# MCU2.net
KiCad netlist of a schematic drawn in Altium Designer
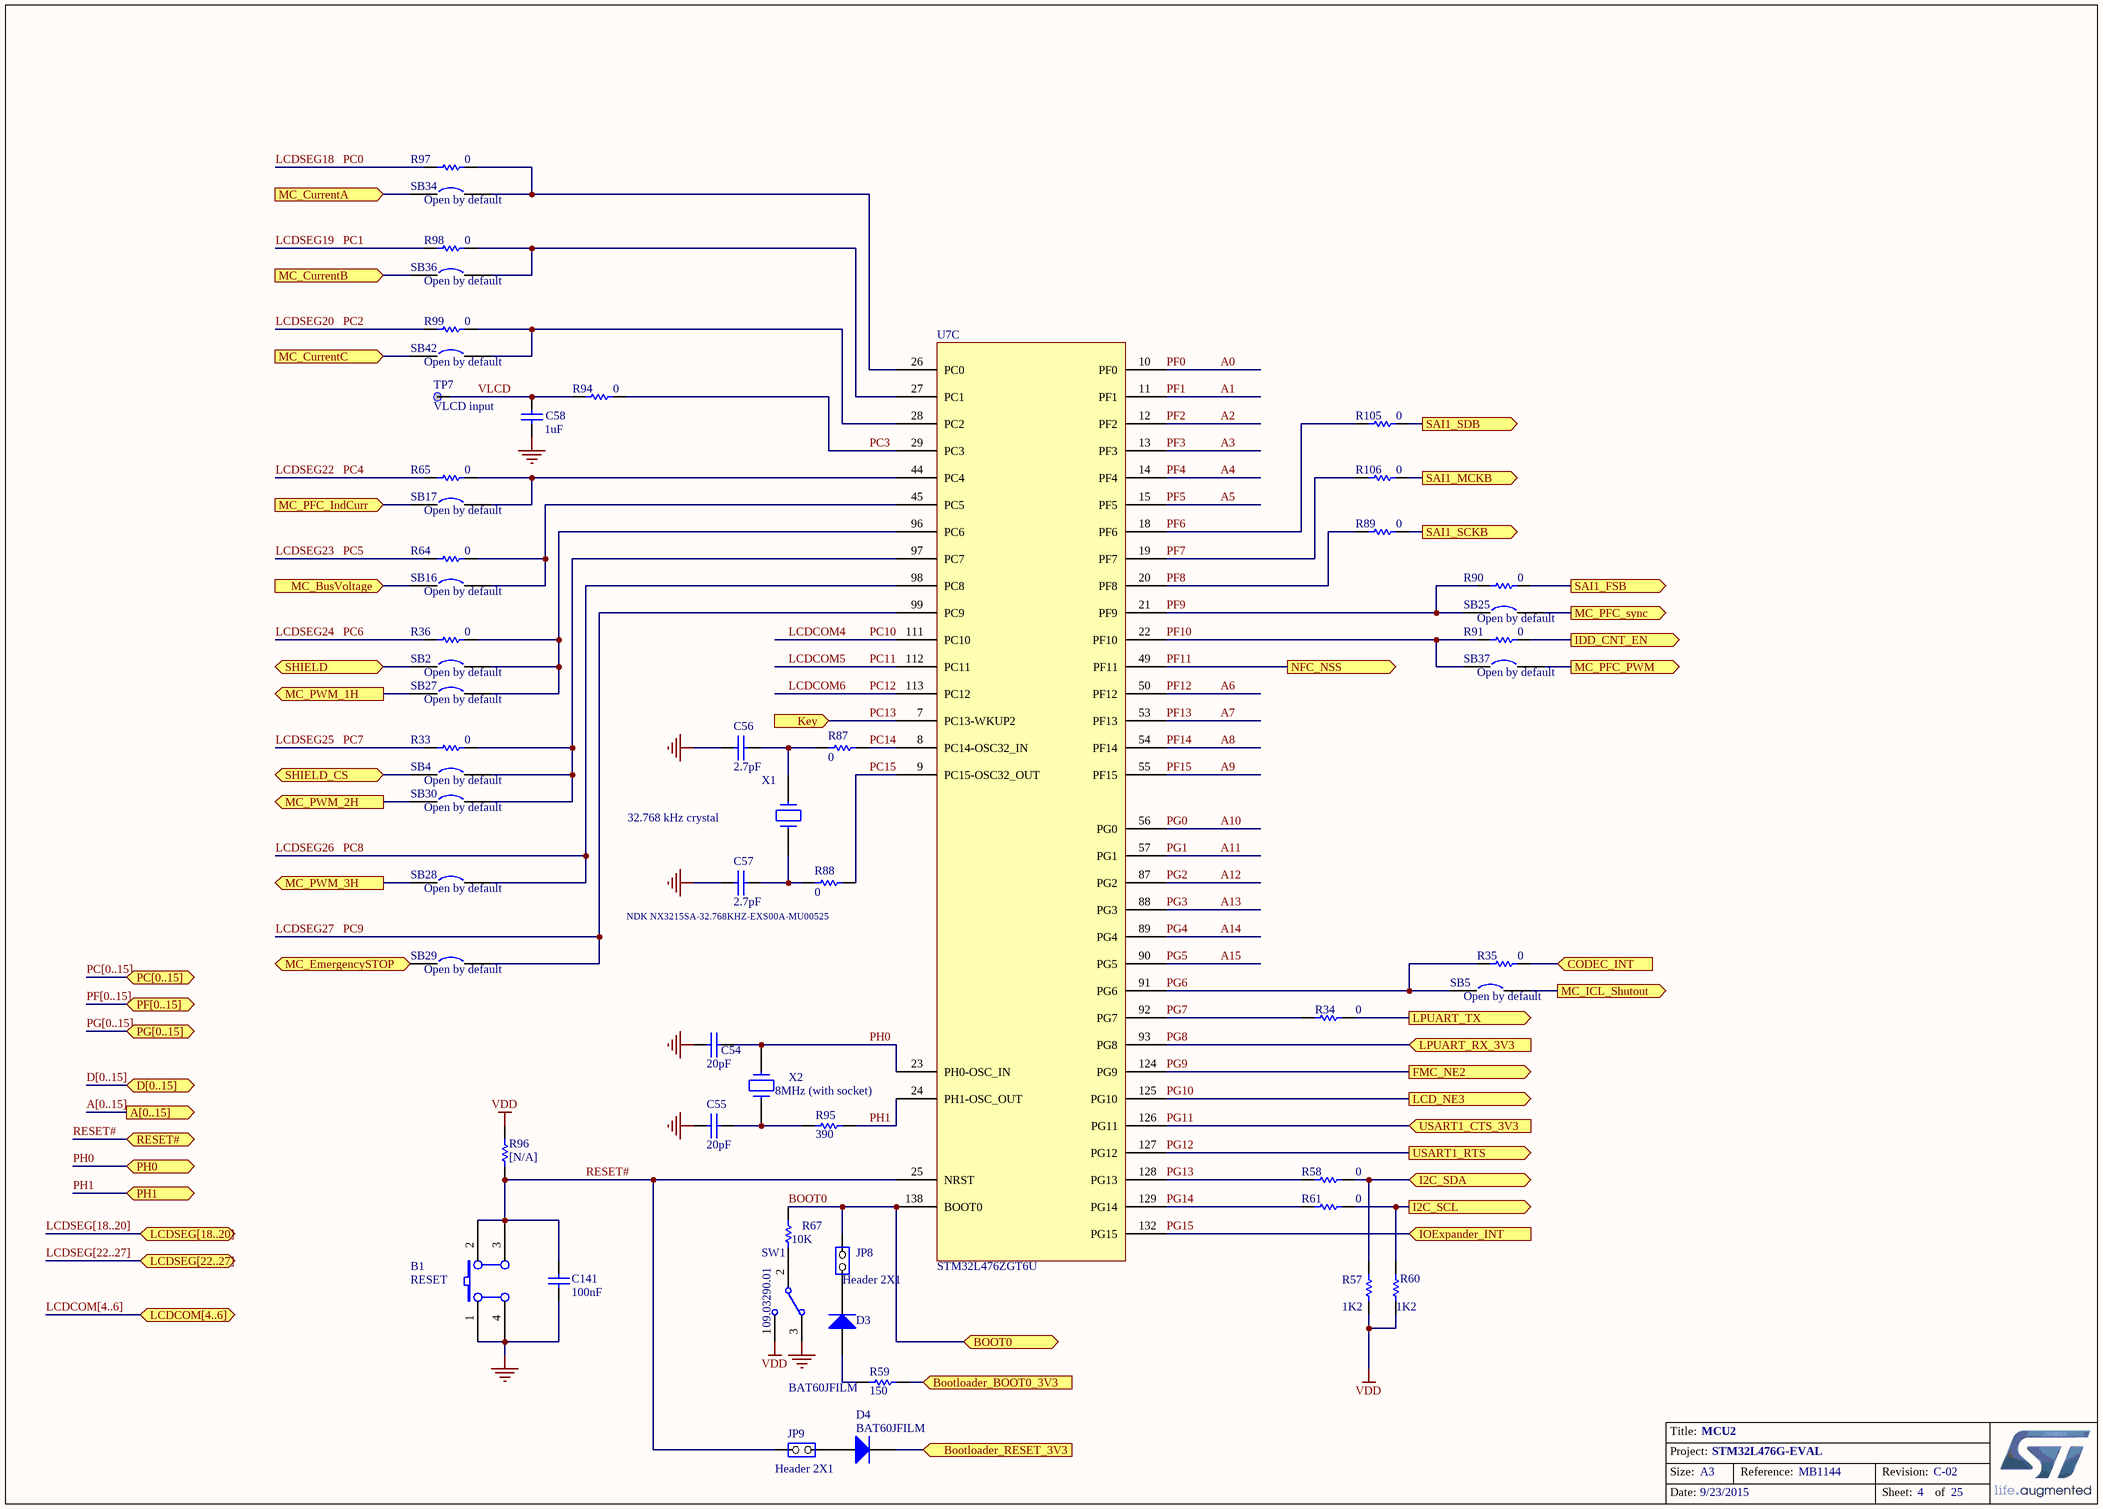
[diagram p0: MCU2.SchDoc]

(export (version "E")
  (design (tool "Eeschema 10.0.6"))
  (components
    (comp (ref "B1")
      (value "RESET")
      (footprint "PB10")
      (description "SE PUSHBUTTON")
      (libsource (lib "Documents") (part "SW PUSHBUTTON"))
    )
    (comp (ref "C54")
      (value "20pF")
      (footprint "0402R")
      (description "Capacitor")
      (libsource (lib "*") (part "CAP"))
    )
    (comp (ref "C55")
      (value "20pF")
      (footprint "0402R")
      (description "Capacitor")
      (libsource (lib "*") (part "CAP"))
    )
    (comp (ref "C56")
      (value "2.7pF")
      (footprint "0603C")
      (description "Capacitor")
      (libsource (lib "") (part "CAP_1"))
    )
    (comp (ref "C57")
      (value "2.7pF")
      (footprint "0603C")
      (description "Capacitor")
      (libsource (lib "") (part "CAP_1"))
    )
    (comp (ref "C58")
      (value "1uF")
      (footprint "0603C")
      (description "Capacitor")
      (fields (field (name "PUBLISHER") "Altium Limited"))
      (libsource (lib "Miscellaneous Devices") (part "CAP"))
    )
    (comp (ref "C141")
      (value "100nF")
      (footprint "0402C")
      (description "Capacitor")
      (fields (field (name "PUBLISHER") "Altium Limited"))
      (libsource (lib "Miscellaneous Devices") (part "CAP"))
    )
    (comp (ref "D3")
      (value "BAT60JFILM")
      (footprint "SOD-323")
      (description "Default Diode")
      (fields (field (name "PUBLISHER") "Altium Limited"))
      (libsource (lib "Miscellaneous Devices") (part "Diode"))
    )
    (comp (ref "D4")
      (value "BAT60JFILM")
      (footprint "SOD-323")
      (description "Default Diode")
      (fields (field (name "PUBLISHER") "Altium Limited"))
      (libsource (lib "Miscellaneous Devices") (part "Diode"))
    )
    (comp (ref "JP8") (value "Header 2X1") (footprint "SIP2") (libsource (lib "*") (part "JP2")))
    (comp (ref "JP9") (value "Header 2X1") (footprint "SIP2") (libsource (lib "*") (part "JP2")))
    (comp (ref "R33")
      (value "0")
      (footprint "SB_0603")
      (description "Resistor")
      (fields (field (name "PUBLISHER") "Altium Limited"))
      (libsource (lib "Miscellaneous Devices") (part "Res1"))
    )
    (comp (ref "R34")
      (value "0")
      (footprint "0603R")
      (description "Resistor")
      (fields (field (name "PUBLISHER") "Altium Limited"))
      (libsource (lib "") (part "Res1_1"))
    )
    (comp (ref "R35")
      (value "0")
      (footprint "SB_0603")
      (description "Resistor")
      (fields (field (name "PUBLISHER") "Altium Limited"))
      (libsource (lib "Miscellaneous Devices") (part "res1"))
    )
    (comp (ref "R36")
      (value "0")
      (footprint "SB_0603")
      (description "Resistor")
      (fields (field (name "PUBLISHER") "Altium Limited"))
      (libsource (lib "Miscellaneous Devices") (part "Res1"))
    )
    (comp (ref "R57")
      (value "1K2")
      (footprint "0402R")
      (description "Resistor")
      (fields (field (name "PUBLISHER") "Altium Limited"))
      (libsource (lib "") (part "Res1_1"))
    )
    (comp (ref "R58")
      (value "0")
      (footprint "0603R")
      (description "Resistor")
      (fields (field (name "PUBLISHER") "Altium Limited"))
      (libsource (lib "") (part "Res1_1"))
    )
    (comp (ref "R59")
      (value "150")
      (footprint "0402R")
      (description "Resistor")
      (fields (field (name "PUBLISHER") "Altium Limited"))
      (libsource (lib "Miscellaneous Devices") (part "res1"))
    )
    (comp (ref "R60")
      (value "1K2")
      (footprint "0402R")
      (description "Resistor")
      (fields (field (name "PUBLISHER") "Altium Limited"))
      (libsource (lib "") (part "Res1_1"))
    )
    (comp (ref "R61")
      (value "0")
      (footprint "0603R")
      (description "Resistor")
      (fields (field (name "PUBLISHER") "Altium Limited"))
      (libsource (lib "") (part "Res1_1"))
    )
    (comp (ref "R64")
      (value "0")
      (footprint "SB_0603")
      (description "Resistor")
      (fields (field (name "PUBLISHER") "Altium Limited"))
      (libsource (lib "Miscellaneous Devices") (part "Res1"))
    )
    (comp (ref "R65")
      (value "0")
      (footprint "SB_0603")
      (description "Resistor")
      (fields (field (name "PUBLISHER") "Altium Limited"))
      (libsource (lib "Miscellaneous Devices") (part "Res1"))
    )
    (comp (ref "R67")
      (value "10K")
      (footprint "0402R")
      (description "Resistor")
      (fields (field (name "PUBLISHER") "Altium Limited"))
      (libsource (lib "Miscellaneous Devices") (part "res1"))
    )
    (comp (ref "R87")
      (value "0")
      (footprint "0603R")
      (description "Resistor")
      (fields (field (name "PUBLISHER") "Altium Limited"))
      (libsource (lib "Miscellaneous Devices") (part "Res1"))
    )
    (comp (ref "R88")
      (value "0")
      (footprint "0603R")
      (description "Resistor")
      (fields (field (name "PUBLISHER") "Altium Limited"))
      (libsource (lib "Miscellaneous Devices") (part "Res1"))
    )
    (comp (ref "R89")
      (value "0")
      (footprint "0603R")
      (description "Resistor")
      (fields (field (name "PUBLISHER") "Altium Limited"))
      (libsource (lib "Miscellaneous Devices") (part "res1"))
    )
    (comp (ref "R90")
      (value "0")
      (footprint "SB_0603")
      (description "Resistor")
      (fields (field (name "PUBLISHER") "Altium Limited"))
      (libsource (lib "Miscellaneous Devices") (part "res1"))
    )
    (comp (ref "R91")
      (value "0")
      (footprint "SB_0603")
      (description "Resistor")
      (fields (field (name "PUBLISHER") "Altium Limited"))
      (libsource (lib "Miscellaneous Devices") (part "res1"))
    )
    (comp (ref "R94")
      (value "0")
      (footprint "0603R")
      (description "Resistor")
      (fields (field (name "PUBLISHER") "Altium Limited"))
      (libsource (lib "Miscellaneous Devices") (part "res1"))
    )
    (comp (ref "R95")
      (value "390")
      (footprint "0603R")
      (description "Resistor")
      (fields (field (name "PUBLISHER") "Altium Limited"))
      (libsource (lib "") (part "Res1_1"))
    )
    (comp (ref "R96")
      (value "[N/A]")
      (footprint "0603R")
      (description "Resistor")
      (fields (field (name "PUBLISHER") "Altium Limited"))
      (libsource (lib "Miscellaneous Devices") (part "res1"))
    )
    (comp (ref "R97")
      (value "0")
      (footprint "SB_0603")
      (description "Resistor")
      (fields (field (name "PUBLISHER") "Altium Limited"))
      (libsource (lib "Miscellaneous Devices") (part "Res1"))
    )
    (comp (ref "R98")
      (value "0")
      (footprint "SB_0603")
      (description "Resistor")
      (fields (field (name "PUBLISHER") "Altium Limited"))
      (libsource (lib "Miscellaneous Devices") (part "Res1"))
    )
    (comp (ref "R99")
      (value "0")
      (footprint "SB_0603")
      (description "Resistor")
      (fields (field (name "PUBLISHER") "Altium Limited"))
      (libsource (lib "Miscellaneous Devices") (part "Res1"))
    )
    (comp (ref "R105")
      (value "0")
      (footprint "0603R")
      (description "Resistor")
      (fields (field (name "PUBLISHER") "Altium Limited"))
      (libsource (lib "Miscellaneous Devices") (part "res1"))
    )
    (comp (ref "R106")
      (value "0")
      (footprint "0603R")
      (description "Resistor")
      (fields (field (name "PUBLISHER") "Altium Limited"))
      (libsource (lib "Miscellaneous Devices") (part "res1"))
    )
    (comp (ref "SB2")
      (value "Open by default")
      (footprint "SB_0603")
      (description "Circuit Breaker")
      (fields (field (name "PUBLISHER") "Altium Limited"))
      (libsource (lib "Miscellaneous Devices") (part "Circuit Breaker"))
    )
    (comp (ref "SB4")
      (value "Open by default")
      (footprint "SB_0603")
      (description "Circuit Breaker")
      (fields (field (name "PUBLISHER") "Altium Limited"))
      (libsource (lib "Miscellaneous Devices") (part "Circuit Breaker"))
    )
    (comp (ref "SB5")
      (value "Open by default")
      (footprint "SB_0603")
      (description "Circuit Breaker")
      (fields (field (name "PUBLISHER") "Altium Limited"))
      (libsource (lib "Miscellaneous Devices") (part "Circuit Breaker"))
    )
    (comp (ref "SB16")
      (value "Open by default")
      (footprint "SB_0603")
      (description "Circuit Breaker")
      (fields (field (name "PUBLISHER") "Altium Limited"))
      (libsource (lib "Miscellaneous Devices") (part "Circuit Breaker"))
    )
    (comp (ref "SB17")
      (value "Open by default")
      (footprint "SB_0603")
      (description "Circuit Breaker")
      (fields (field (name "PUBLISHER") "Altium Limited"))
      (libsource (lib "Miscellaneous Devices") (part "Circuit Breaker"))
    )
    (comp (ref "SB25")
      (value "Open by default")
      (footprint "SB_0603")
      (description "Circuit Breaker")
      (fields (field (name "PUBLISHER") "Altium Limited"))
      (libsource (lib "Miscellaneous Devices") (part "Circuit Breaker"))
    )
    (comp (ref "SB27")
      (value "Open by default")
      (footprint "SB_0603")
      (description "Circuit Breaker")
      (fields (field (name "PUBLISHER") "Altium Limited"))
      (libsource (lib "Miscellaneous Devices") (part "Circuit Breaker"))
    )
    (comp (ref "SB28")
      (value "Open by default")
      (footprint "SB_0603")
      (description "Circuit Breaker")
      (fields (field (name "PUBLISHER") "Altium Limited"))
      (libsource (lib "Miscellaneous Devices") (part "Circuit Breaker"))
    )
    (comp (ref "SB29")
      (value "Open by default")
      (footprint "SB_0603")
      (description "Circuit Breaker")
      (fields (field (name "PUBLISHER") "Altium Limited"))
      (libsource (lib "Miscellaneous Devices") (part "Circuit Breaker"))
    )
    (comp (ref "SB30")
      (value "Open by default")
      (footprint "SB_0603")
      (description "Circuit Breaker")
      (fields (field (name "PUBLISHER") "Altium Limited"))
      (libsource (lib "Miscellaneous Devices") (part "Circuit Breaker"))
    )
    (comp (ref "SB34")
      (value "Open by default")
      (footprint "SB_0603")
      (description "Circuit Breaker")
      (fields (field (name "PUBLISHER") "Altium Limited"))
      (libsource (lib "Miscellaneous Devices") (part "Circuit Breaker"))
    )
    (comp (ref "SB36")
      (value "Open by default")
      (footprint "SB_0603")
      (description "Circuit Breaker")
      (fields (field (name "PUBLISHER") "Altium Limited"))
      (libsource (lib "Miscellaneous Devices") (part "Circuit Breaker"))
    )
    (comp (ref "SB37")
      (value "Open by default")
      (footprint "SB_0603")
      (description "Circuit Breaker")
      (fields (field (name "PUBLISHER") "Altium Limited"))
      (libsource (lib "Miscellaneous Devices") (part "Circuit Breaker"))
    )
    (comp (ref "SB42")
      (value "Open by default")
      (footprint "SB_0603")
      (description "Circuit Breaker")
      (fields (field (name "PUBLISHER") "Altium Limited"))
      (libsource (lib "Miscellaneous Devices") (part "Circuit Breaker"))
    )
    (comp (ref "SW1")
      (value "09.03290.01")
      (footprint "SW1_3TH_2R54_10X2R5")
      (description "SPDT Subminiature Toggle Switch, Right Angle Mounting, Vertical Actuation")
      (fields (field (name "PUBLISHER") "Altium Limited"))
      (libsource (lib "Miscellaneous Devices") (part "SW-SPDT"))
    )
    (comp (ref "TP7")
      (value "[N/A]")
      (footprint "TP")
      (fields (field (name "TP NAME") "VLCD input"))
      (libsource (lib "orca2") (part "TP"))
    )
    (comp (ref "U7")
      (value "STM32L476ZGT6U")
      (footprint "TQFP144_0R5_22X22_SOCKET")
      (libsource (lib "MB1144") (part "STM32L476_TQFP144"))
    )
    (comp (ref "X1")
      (value "NDK NX3215SA-32.768KHZ-EXS00A-MU00525")
      (footprint "XTAL_2SM_3R2X1R5")
      (description "Crystal")
      (libsource (lib "MB1167") (part "CRYSTAL_32K"))
    )
    (comp (ref "X2")
      (value "8MHz (with socket)")
      (footprint "XTAL_SOCKET")
      (description "Crystal")
      (libsource (lib "*") (part "CRYSTAL"))
    )
  )
  (nets
    (net (code "17") (name "/A10") (class "Default")
      (node (ref "U7") (pin "56") (pinfunction "PG0_56") (pintype "passive"))
    )
    (net (code "18") (name "/A11") (class "Default")
      (node (ref "U7") (pin "57") (pinfunction "PG1_57") (pintype "passive"))
    )
    (net (code "19") (name "/A12") (class "Default")
      (node (ref "U7") (pin "87") (pinfunction "PG2_87") (pintype "passive"))
    )
    (net (code "20") (name "/A13") (class "Default")
      (node (ref "U7") (pin "88") (pinfunction "PG3_88") (pintype "passive"))
    )
    (net (code "21") (name "/A14") (class "Default")
      (node (ref "U7") (pin "89") (pinfunction "PG4_89") (pintype "passive"))
    )
    (net (code "22") (name "/A15") (class "Default")
      (node (ref "U7") (pin "90") (pinfunction "PG5_90") (pintype "passive"))
    )
    (net (code "24") (name "/BOOT0") (class "Default")
      (node (ref "JP8") (pin "1") (pinfunction "COMMON_1") (pintype "passive"))
      (node (ref "R67") (pin "1") (pinfunction "1_1") (pintype "passive"))
      (node (ref "U7") (pin "138") (pinfunction "BOOT0_138") (pintype "passive"))
    )
    (net (code "25") (name "/Bootloader_BOOT0_3V3") (class "Default")
      (node (ref "R59") (pin "2") (pinfunction "2_2") (pintype "passive"))
    )
    (net (code "26") (name "/Bootloader_RESET_3V3") (class "Default")
      (node (ref "D4") (pin "2") (pinfunction "K_2") (pintype "passive"))
    )
    (net (code "27") (name "/CODEC_INT") (class "Default")
      (node (ref "R35") (pin "1") (pinfunction "1_1") (pintype "passive"))
    )
    (net (code "29") (name "/I2C_SCL") (class "Default")
      (node (ref "R60") (pin "1") (pinfunction "1_1") (pintype "passive"))
      (node (ref "R61") (pin "1") (pinfunction "1_1") (pintype "passive"))
    )
    (net (code "30") (name "/I2C_SDA") (class "Default")
      (node (ref "R57") (pin "1") (pinfunction "1_1") (pintype "passive"))
      (node (ref "R58") (pin "1") (pinfunction "1_1") (pintype "passive"))
    )
    (net (code "31") (name "/IDD_CNT_EN") (class "Default")
      (node (ref "R91") (pin "1") (pinfunction "1_1") (pintype "passive"))
    )
    (net (code "35") (name "/LPUART_TX") (class "Default")
      (node (ref "R34") (pin "1") (pinfunction "1_1") (pintype "passive"))
    )
    (net (code "36") (name "/MC_BusVoltage") (class "Default")
      (node (ref "SB16") (pin "1") (pinfunction "1_1") (pintype "passive"))
    )
    (net (code "37") (name "/MC_CurrentA") (class "Default")
      (node (ref "SB34") (pin "1") (pinfunction "1_1") (pintype "passive"))
    )
    (net (code "38") (name "/MC_CurrentB") (class "Default")
      (node (ref "SB36") (pin "1") (pinfunction "1_1") (pintype "passive"))
    )
    (net (code "39") (name "/MC_CurrentC") (class "Default")
      (node (ref "SB42") (pin "1") (pinfunction "1_1") (pintype "passive"))
    )
    (net (code "40") (name "/MC_EmergencySTOP") (class "Default")
      (node (ref "SB29") (pin "1") (pinfunction "1_1") (pintype "passive"))
    )
    (net (code "41") (name "/MC_ICL_Shutout") (class "Default")
      (node (ref "SB5") (pin "2") (pinfunction "2_2") (pintype "passive"))
    )
    (net (code "42") (name "/MC_PFC_IndCurr") (class "Default")
      (node (ref "SB17") (pin "1") (pinfunction "1_1") (pintype "passive"))
    )
    (net (code "43") (name "/MC_PFC_PWM") (class "Default")
      (node (ref "SB37") (pin "2") (pinfunction "2_2") (pintype "passive"))
    )
    (net (code "44") (name "/MC_PFC_sync") (class "Default")
      (node (ref "SB25") (pin "2") (pinfunction "2_2") (pintype "passive"))
    )
    (net (code "45") (name "/MC_PWM_1H") (class "Default")
      (node (ref "SB27") (pin "1") (pinfunction "1_1") (pintype "passive"))
    )
    (net (code "46") (name "/MC_PWM_2H") (class "Default")
      (node (ref "SB30") (pin "1") (pinfunction "1_1") (pintype "passive"))
    )
    (net (code "47") (name "/MC_PWM_3H") (class "Default")
      (node (ref "SB28") (pin "1") (pinfunction "1_1") (pintype "passive"))
    )
    (net (code "48") (name "/PC0") (class "Default")
      (node (ref "R97") (pin "1") (pinfunction "1_1") (pintype "passive"))
    )
    (net (code "49") (name "/PC1") (class "Default")
      (node (ref "R98") (pin "1") (pinfunction "1_1") (pintype "passive"))
    )
    (net (code "50") (name "/PC2") (class "Default")
      (node (ref "R99") (pin "1") (pinfunction "1_1") (pintype "passive"))
    )
    (net (code "51") (name "/PC3") (class "Default")
      (node (ref "R94") (pin "1") (pinfunction "1_1") (pintype "passive"))
      (node (ref "U7") (pin "29") (pinfunction "PC3_29") (pintype "passive"))
    )
    (net (code "52") (name "/PC4") (class "Default")
      (node (ref "R65") (pin "1") (pinfunction "1_1") (pintype "passive"))
    )
    (net (code "53") (name "/PC5") (class "Default")
      (node (ref "R64") (pin "1") (pinfunction "1_1") (pintype "passive"))
    )
    (net (code "54") (name "/PC6") (class "Default")
      (node (ref "R36") (pin "1") (pinfunction "1_1") (pintype "passive"))
    )
    (net (code "55") (name "/PC7") (class "Default")
      (node (ref "R33") (pin "1") (pinfunction "1_1") (pintype "passive"))
    )
    (net (code "56") (name "/PC8") (class "Default")
      (node (ref "SB28") (pin "2") (pinfunction "2_2") (pintype "passive"))
      (node (ref "U7") (pin "98") (pinfunction "PC8_98") (pintype "passive"))
    )
    (net (code "57") (name "/PC9") (class "Default")
      (node (ref "SB29") (pin "2") (pinfunction "2_2") (pintype "passive"))
      (node (ref "U7") (pin "99") (pinfunction "PC9_99") (pintype "passive"))
    )
    (net (code "58") (name "/PC10") (class "Default")
      (node (ref "U7") (pin "111") (pinfunction "PC10_111") (pintype "passive"))
    )
    (net (code "59") (name "/PC11") (class "Default")
      (node (ref "U7") (pin "112") (pinfunction "PC11_112") (pintype "passive"))
    )
    (net (code "60") (name "/PC12") (class "Default")
      (node (ref "U7") (pin "113") (pinfunction "PC12_113") (pintype "passive"))
    )
    (net (code "61") (name "/PC13") (class "Default")
      (node (ref "U7") (pin "7") (pinfunction "PC13-WKUP2_7") (pintype "passive"))
    )
    (net (code "62") (name "/PC14") (class "Default")
      (node (ref "R87") (pin "2") (pinfunction "2_2") (pintype "passive"))
      (node (ref "U7") (pin "8") (pinfunction "PC14-OSC32_IN_8") (pintype "passive"))
    )
    (net (code "63") (name "/PC15") (class "Default")
      (node (ref "R88") (pin "2") (pinfunction "2_2") (pintype "passive"))
      (node (ref "U7") (pin "9") (pinfunction "PC15-OSC32_OUT_9") (pintype "passive"))
    )
    (net (code "65") (name "/PF0") (class "Default")
      (node (ref "U7") (pin "10") (pinfunction "PF0_10") (pintype "passive"))
    )
    (net (code "66") (name "/PF1") (class "Default")
      (node (ref "U7") (pin "11") (pinfunction "PF1_11") (pintype "passive"))
    )
    (net (code "67") (name "/PF2") (class "Default")
      (node (ref "U7") (pin "12") (pinfunction "PF2_12") (pintype "passive"))
    )
    (net (code "68") (name "/PF3") (class "Default")
      (node (ref "U7") (pin "13") (pinfunction "PF3_13") (pintype "passive"))
    )
    (net (code "69") (name "/PF4") (class "Default")
      (node (ref "U7") (pin "14") (pinfunction "PF4_14") (pintype "passive"))
    )
    (net (code "70") (name "/PF5") (class "Default")
      (node (ref "U7") (pin "15") (pinfunction "PF5_15") (pintype "passive"))
    )
    (net (code "71") (name "/PF6") (class "Default")
      (node (ref "R105") (pin "2") (pinfunction "2_2") (pintype "passive"))
      (node (ref "U7") (pin "18") (pinfunction "PF6_18") (pintype "passive"))
    )
    (net (code "72") (name "/PF7") (class "Default")
      (node (ref "R106") (pin "2") (pinfunction "2_2") (pintype "passive"))
      (node (ref "U7") (pin "19") (pinfunction "PF7_19") (pintype "passive"))
    )
    (net (code "73") (name "/PF8") (class "Default")
      (node (ref "R89") (pin "2") (pinfunction "2_2") (pintype "passive"))
      (node (ref "U7") (pin "20") (pinfunction "PF8_20") (pintype "passive"))
    )
    (net (code "74") (name "/PF9") (class "Default")
      (node (ref "R90") (pin "2") (pinfunction "2_2") (pintype "passive"))
      (node (ref "SB25") (pin "1") (pinfunction "1_1") (pintype "passive"))
      (node (ref "U7") (pin "21") (pinfunction "PF9_21") (pintype "passive"))
    )
    (net (code "75") (name "/PF10") (class "Default")
      (node (ref "R91") (pin "2") (pinfunction "2_2") (pintype "passive"))
      (node (ref "SB37") (pin "1") (pinfunction "1_1") (pintype "passive"))
      (node (ref "U7") (pin "22") (pinfunction "PF10_22") (pintype "passive"))
    )
    (net (code "76") (name "/PF11") (class "Default")
      (node (ref "U7") (pin "49") (pinfunction "PF11_49") (pintype "passive"))
    )
    (net (code "77") (name "/PF12") (class "Default")
      (node (ref "U7") (pin "50") (pinfunction "PF12_50") (pintype "passive"))
    )
    (net (code "78") (name "/PF13") (class "Default")
      (node (ref "U7") (pin "53") (pinfunction "PF13_53") (pintype "passive"))
    )
    (net (code "79") (name "/PF14") (class "Default")
      (node (ref "U7") (pin "54") (pinfunction "PF14_54") (pintype "passive"))
    )
    (net (code "80") (name "/PF15") (class "Default")
      (node (ref "U7") (pin "55") (pinfunction "PF15_55") (pintype "passive"))
    )
    (net (code "82") (name "/PG6") (class "Default")
      (node (ref "R35") (pin "2") (pinfunction "2_2") (pintype "passive"))
      (node (ref "SB5") (pin "1") (pinfunction "1_1") (pintype "passive"))
      (node (ref "U7") (pin "91") (pinfunction "PG6_91") (pintype "passive"))
    )
    (net (code "83") (name "/PG7") (class "Default")
      (node (ref "R34") (pin "2") (pinfunction "2_2") (pintype "passive"))
      (node (ref "U7") (pin "92") (pinfunction "PG7_92") (pintype "passive"))
    )
    (net (code "84") (name "/PG8") (class "Default")
      (node (ref "U7") (pin "93") (pinfunction "PG8_93") (pintype "passive"))
    )
    (net (code "85") (name "/PG9") (class "Default")
      (node (ref "U7") (pin "124") (pinfunction "PG9_124") (pintype "passive"))
    )
    (net (code "86") (name "/PG10") (class "Default")
      (node (ref "U7") (pin "125") (pinfunction "PG10_125") (pintype "passive"))
    )
    (net (code "87") (name "/PG11") (class "Default")
      (node (ref "U7") (pin "126") (pinfunction "PG11_126") (pintype "passive"))
    )
    (net (code "88") (name "/PG12") (class "Default")
      (node (ref "U7") (pin "127") (pinfunction "PG12_127") (pintype "passive"))
    )
    (net (code "89") (name "/PG13") (class "Default")
      (node (ref "R58") (pin "2") (pinfunction "2_2") (pintype "passive"))
      (node (ref "U7") (pin "128") (pinfunction "PG13_128") (pintype "passive"))
    )
    (net (code "90") (name "/PG14") (class "Default")
      (node (ref "R61") (pin "2") (pinfunction "2_2") (pintype "passive"))
      (node (ref "U7") (pin "129") (pinfunction "PG14_129") (pintype "passive"))
    )
    (net (code "91") (name "/PG15") (class "Default")
      (node (ref "U7") (pin "132") (pinfunction "PG15_132") (pintype "passive"))
    )
    (net (code "93") (name "/PH0") (class "Default")
      (node (ref "C54") (pin "1") (pinfunction "1_1") (pintype "passive"))
      (node (ref "U7") (pin "23") (pinfunction "PH0-OSC_IN_23") (pintype "passive"))
      (node (ref "X2") (pin "2") (pinfunction "2_2") (pintype "passive"))
    )
    (net (code "94") (name "/PH1") (class "Default")
      (node (ref "R95") (pin "1") (pinfunction "1_1") (pintype "passive"))
      (node (ref "U7") (pin "24") (pinfunction "PH1-OSC_OUT_24") (pintype "passive"))
    )
    (net (code "95") (name "/RESET#") (class "Default")
      (node (ref "B1") (pin "2") (pinfunction "B0_2") (pintype "passive"))
      (node (ref "B1") (pin "3") (pinfunction "B1_3") (pintype "passive"))
      (node (ref "C141") (pin "2") (pinfunction "2_2") (pintype "passive"))
      (node (ref "JP9") (pin "1") (pinfunction "COMMON_1") (pintype "passive"))
      (node (ref "R96") (pin "1") (pinfunction "1_1") (pintype "passive"))
      (node (ref "U7") (pin "25") (pinfunction "NRST_25") (pintype "passive"))
    )
    (net (code "96") (name "/SAI1_FSB") (class "Default")
      (node (ref "R90") (pin "1") (pinfunction "1_1") (pintype "passive"))
    )
    (net (code "97") (name "/SAI1_MCKB") (class "Default")
      (node (ref "R106") (pin "1") (pinfunction "1_1") (pintype "passive"))
    )
    (net (code "98") (name "/SAI1_SCKB") (class "Default")
      (node (ref "R89") (pin "1") (pinfunction "1_1") (pintype "passive"))
    )
    (net (code "99") (name "/SAI1_SDB") (class "Default")
      (node (ref "R105") (pin "1") (pinfunction "1_1") (pintype "passive"))
    )
    (net (code "100") (name "/SHIELD") (class "Default")
      (node (ref "SB2") (pin "1") (pinfunction "1_1") (pintype "passive"))
    )
    (net (code "101") (name "/SHIELD_CS") (class "Default")
      (node (ref "SB4") (pin "1") (pinfunction "1_1") (pintype "passive"))
    )
    (net (code "102") (name "/VLCD") (class "Default")
      (node (ref "C58") (pin "2") (pinfunction "2_2") (pintype "passive"))
      (node (ref "R94") (pin "2") (pinfunction "2_2") (pintype "passive"))
      (node (ref "TP7") (pin "1") (pinfunction "1_1") (pintype "passive"))
    )
    (net (code "103") (name "GND") (class "Default")
      (node (ref "B1") (pin "1") (pinfunction "A0_1") (pintype "passive"))
      (node (ref "B1") (pin "4") (pinfunction "A1_4") (pintype "passive"))
      (node (ref "C141") (pin "1") (pinfunction "1_1") (pintype "passive"))
      (node (ref "C54") (pin "2") (pinfunction "2_2") (pintype "passive"))
      (node (ref "C55") (pin "2") (pinfunction "2_2") (pintype "passive"))
      (node (ref "C56") (pin "2") (pinfunction "2_2") (pintype "passive"))
      (node (ref "C57") (pin "2") (pinfunction "2_2") (pintype "passive"))
      (node (ref "C58") (pin "1") (pinfunction "1_1") (pintype "passive"))
      (node (ref "SW1") (pin "3") (pintype "passive"))
    )
    (net (code "104") (name "Net-(C55-Pad1)") (class "Default")
      (node (ref "C55") (pin "1") (pinfunction "1_1") (pintype "passive"))
      (node (ref "R95") (pin "2") (pinfunction "2_2") (pintype "passive"))
      (node (ref "X2") (pin "1") (pinfunction "1_1") (pintype "passive"))
    )
    (net (code "105") (name "Net-(C56-Pad1)") (class "Default")
      (node (ref "C56") (pin "1") (pinfunction "1_1") (pintype "passive"))
      (node (ref "R87") (pin "1") (pinfunction "1_1") (pintype "passive"))
      (node (ref "X1") (pin "2") (pinfunction "2_2") (pintype "passive"))
    )
    (net (code "106") (name "Net-(C57-Pad1)") (class "Default")
      (node (ref "C57") (pin "1") (pinfunction "1_1") (pintype "passive"))
      (node (ref "R88") (pin "1") (pinfunction "1_1") (pintype "passive"))
      (node (ref "X1") (pin "1") (pinfunction "1_1") (pintype "passive"))
    )
    (net (code "107") (name "Net-(D3-A)") (class "Default")
      (node (ref "D3") (pin "1") (pinfunction "A_1") (pintype "passive"))
      (node (ref "R59") (pin "1") (pinfunction "1_1") (pintype "passive"))
    )
    (net (code "108") (name "Net-(D3-K)") (class "Default")
      (node (ref "D3") (pin "2") (pinfunction "K_2") (pintype "passive"))
      (node (ref "JP8") (pin "2") (pinfunction "NO_2") (pintype "passive"))
    )
    (net (code "109") (name "Net-(D4-A)") (class "Default")
      (node (ref "D4") (pin "1") (pinfunction "A_1") (pintype "passive"))
      (node (ref "JP9") (pin "2") (pinfunction "NO_2") (pintype "passive"))
    )
    (net (code "110") (name "Net-(R67-Pad2)") (class "Default")
      (node (ref "R67") (pin "2") (pinfunction "2_2") (pintype "passive"))
      (node (ref "SW1") (pin "2") (pintype "passive"))
    )
    (net (code "111") (name "Net-(U7C-PC0)") (class "Default")
      (node (ref "R97") (pin "2") (pinfunction "2_2") (pintype "passive"))
      (node (ref "SB34") (pin "2") (pinfunction "2_2") (pintype "passive"))
      (node (ref "U7") (pin "26") (pinfunction "PC0_26") (pintype "passive"))
    )
    (net (code "112") (name "Net-(U7C-PC1)") (class "Default")
      (node (ref "R98") (pin "2") (pinfunction "2_2") (pintype "passive"))
      (node (ref "SB36") (pin "2") (pinfunction "2_2") (pintype "passive"))
      (node (ref "U7") (pin "27") (pinfunction "PC1_27") (pintype "passive"))
    )
    (net (code "113") (name "Net-(U7C-PC2)") (class "Default")
      (node (ref "R99") (pin "2") (pinfunction "2_2") (pintype "passive"))
      (node (ref "SB42") (pin "2") (pinfunction "2_2") (pintype "passive"))
      (node (ref "U7") (pin "28") (pinfunction "PC2_28") (pintype "passive"))
    )
    (net (code "114") (name "Net-(U7C-PC4)") (class "Default")
      (node (ref "R65") (pin "2") (pinfunction "2_2") (pintype "passive"))
      (node (ref "SB17") (pin "2") (pinfunction "2_2") (pintype "passive"))
      (node (ref "U7") (pin "44") (pinfunction "PC4_44") (pintype "passive"))
    )
    (net (code "115") (name "Net-(U7C-PC5)") (class "Default")
      (node (ref "R64") (pin "2") (pinfunction "2_2") (pintype "passive"))
      (node (ref "SB16") (pin "2") (pinfunction "2_2") (pintype "passive"))
      (node (ref "U7") (pin "45") (pinfunction "PC5_45") (pintype "passive"))
    )
    (net (code "116") (name "Net-(U7C-PC6)") (class "Default")
      (node (ref "R36") (pin "2") (pinfunction "2_2") (pintype "passive"))
      (node (ref "SB2") (pin "2") (pinfunction "2_2") (pintype "passive"))
      (node (ref "SB27") (pin "2") (pinfunction "2_2") (pintype "passive"))
      (node (ref "U7") (pin "96") (pinfunction "PC6_96") (pintype "passive"))
    )
    (net (code "117") (name "Net-(U7C-PC7)") (class "Default")
      (node (ref "R33") (pin "2") (pinfunction "2_2") (pintype "passive"))
      (node (ref "SB30") (pin "2") (pinfunction "2_2") (pintype "passive"))
      (node (ref "SB4") (pin "2") (pinfunction "2_2") (pintype "passive"))
      (node (ref "U7") (pin "97") (pinfunction "PC7_97") (pintype "passive"))
    )
    (net (code "118") (name "VDD") (class "Default")
      (node (ref "R57") (pin "2") (pinfunction "2_2") (pintype "passive"))
      (node (ref "R60") (pin "2") (pinfunction "2_2") (pintype "passive"))
      (node (ref "R96") (pin "2") (pinfunction "2_2") (pintype "passive"))
      (node (ref "SW1") (pin "1") (pintype "passive"))
    )
  )
)
